# LPC1768_0.net
KiCad netlist of a schematic drawn in Altium Designer
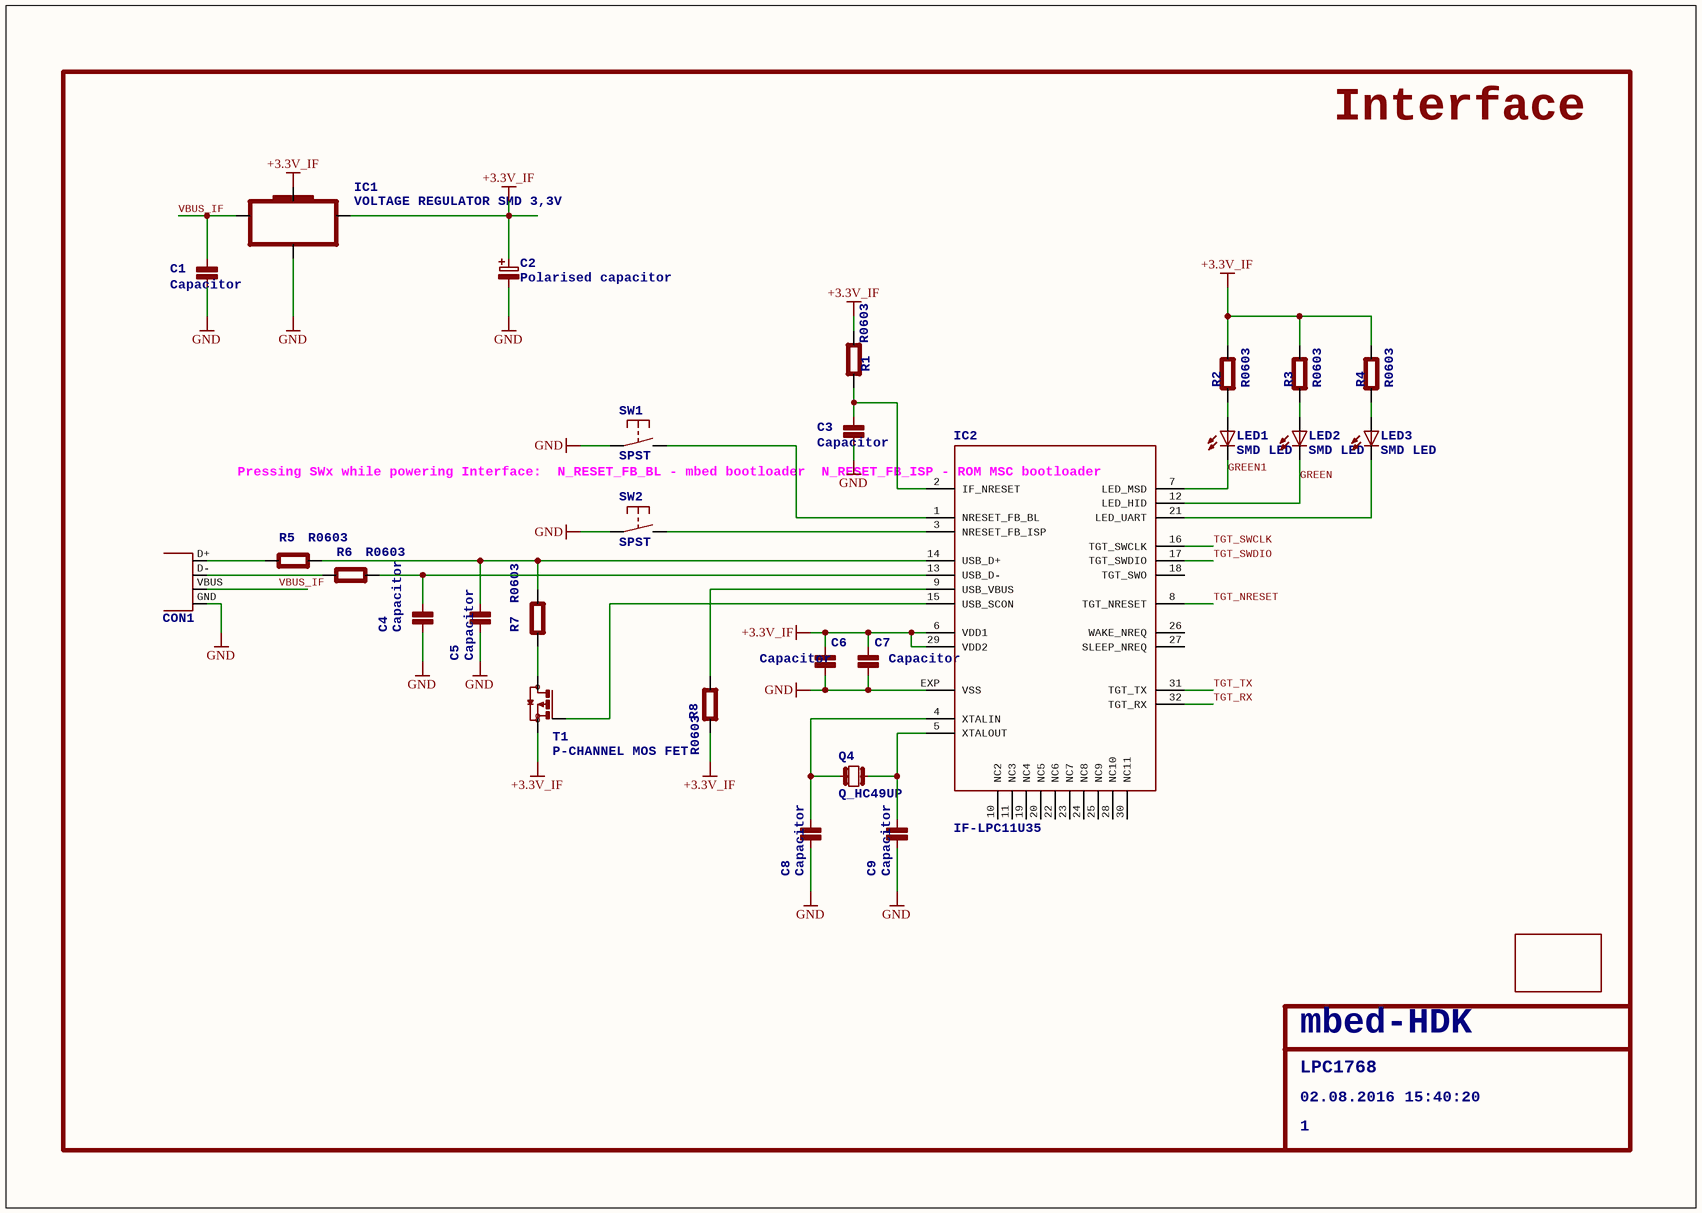
[diagram p0: LPC1768_0.SchDoc]

(export (version "E")
  (design (tool "Eeschema 10.0.6"))
  (components
    (comp (ref "C1") (value "Capacitor") (footprint "0603") (libsource (lib "mbed-HDK") (part "C0603")))
    (comp (ref "C2")
      (value "Polarised capacitor")
      (footprint "CASE-B")
      (libsource (lib "mbed-HDK") (part "C-POLB"))
    )
    (comp (ref "C3") (value "Capacitor") (footprint "0603") (libsource (lib "mbed-HDK") (part "C0603")))
    (comp (ref "C4") (value "Capacitor") (footprint "0603") (libsource (lib "") (part "C0603_1")))
    (comp (ref "C5") (value "Capacitor") (footprint "0603") (libsource (lib "") (part "C0603_1")))
    (comp (ref "C6") (value "Capacitor") (footprint "0603") (libsource (lib "mbed-HDK") (part "C0603")))
    (comp (ref "C7") (value "Capacitor") (footprint "0603") (libsource (lib "mbed-HDK") (part "C0603")))
    (comp (ref "C8") (value "Capacitor") (footprint "0603") (libsource (lib "") (part "C0603_1")))
    (comp (ref "C9") (value "Capacitor") (footprint "0603") (libsource (lib "") (part "C0603_1")))
    (comp (ref "CON1")
      (value "USB Connectors")
      (footprint "USB-MB-S")
      (libsource (lib "mbed-HDK") (part "USB-MB-S"))
    )
    (comp (ref "IC1")
      (value "VOLTAGE REGULATOR SMD 3,3V")
      (footprint "SOT223")
      (libsource (lib "mbed-HDK") (part "LD1117S33"))
    )
    (comp (ref "IC2")
      (value "IF-LPC11U35")
      (footprint "HVQFN33")
      (libsource (lib "mbed-HDK") (part "IF-LPC11U35"))
    )
    (comp (ref "LED1")
      (value "SMD LED")
      (footprint "CHIPLED_0603")
      (libsource (lib "mbed-HDK") (part "LED0603"))
    )
    (comp (ref "LED2")
      (value "SMD LED")
      (footprint "CHIPLED_0603")
      (libsource (lib "mbed-HDK") (part "LED0603"))
    )
    (comp (ref "LED3")
      (value "SMD LED")
      (footprint "CHIPLED_0603")
      (libsource (lib "mbed-HDK") (part "LED0603"))
    )
    (comp (ref "Q4") (value "Q_HC49UP") (footprint "HC49UP") (libsource (lib "mbed-HDK") (part "Q_HC49UP")))
    (comp (ref "R1") (value "R0603") (footprint "0603") (libsource (lib "mbed-HDK") (part "R0603")))
    (comp (ref "R2") (value "R0603") (footprint "0603") (libsource (lib "mbed-HDK") (part "R0603")))
    (comp (ref "R3") (value "R0603") (footprint "0603") (libsource (lib "mbed-HDK") (part "R0603")))
    (comp (ref "R4") (value "R0603") (footprint "0603") (libsource (lib "mbed-HDK") (part "R0603")))
    (comp (ref "R5") (value "R0603") (footprint "0603") (libsource (lib "mbed-HDK") (part "R0603")))
    (comp (ref "R6") (value "R0603") (footprint "0603") (libsource (lib "mbed-HDK") (part "R0603")))
    (comp (ref "R7") (value "R0603") (footprint "0603") (libsource (lib "mbed-HDK") (part "R0603")))
    (comp (ref "R8") (value "R0603") (footprint "0603") (libsource (lib "mbed-HDK") (part "R0603")))
    (comp (ref "SS1")
      (value "MBED-ENABLED-LOGOMEDIUM")
      (footprint "MBED-ENABLED-LOGO-500X500-MIL")
      (libsource (lib "mbed-HDK") (part "MBED-ENABLED-LOGOMEDIUM"))
    )
    (comp (ref "SW1") (value "SPST") (footprint "DTSM-32S-B") (libsource (lib "mbed-HDK") (part "SPST")))
    (comp (ref "SW2") (value "SPST") (footprint "DTSM-32S-B") (libsource (lib "mbed-HDK") (part "SPST")))
    (comp (ref "T1")
      (value "P-CHANNEL MOS FET")
      (footprint "SOT23")
      (libsource (lib "mbed-HDK") (part "BSS84"))
    )
  )
  (nets
    (net (code "1") (name "+3.3V_IF") (class "Default")
      (node (ref "C2") (pin "1") (pinfunction "1_1") (pintype "passive"))
      (node (ref "C6") (pin "1") (pinfunction "P$1_1") (pintype "passive"))
      (node (ref "C7") (pin "1") (pinfunction "P$1_1") (pintype "passive"))
      (node (ref "IC1") (pin "2") (pinfunction "OUT_2") (pintype "passive"))
      (node (ref "IC1") (pin "4") (pinfunction "K_4") (pintype "passive"))
      (node (ref "IC2") (pin "29") (pinfunction "VDD2_29") (pintype "passive"))
      (node (ref "IC2") (pin "6") (pinfunction "VDD1_6") (pintype "passive"))
      (node (ref "R1") (pin "2") (pinfunction "P$2_2") (pintype "passive"))
      (node (ref "R2") (pin "1") (pinfunction "P$1_1") (pintype "passive"))
      (node (ref "R3") (pin "1") (pinfunction "P$1_1") (pintype "passive"))
      (node (ref "R4") (pin "1") (pinfunction "P$1_1") (pintype "passive"))
      (node (ref "R8") (pin "2") (pinfunction "P$2_2") (pintype "passive"))
      (node (ref "T1") (pin "2") (pinfunction "S_2") (pintype "passive"))
    )
    (net (code "2") (name "/GREEN") (class "Default")
      (node (ref "IC2") (pin "12") (pinfunction "LED_HID_12") (pintype "passive"))
      (node (ref "LED2") (pin "C") (pinfunction "C_C") (pintype "passive"))
    )
    (net (code "3") (name "/GREEN1") (class "Default")
      (node (ref "IC2") (pin "7") (pinfunction "LED_MSD_7") (pintype "passive"))
      (node (ref "LED1") (pin "C") (pinfunction "C_C") (pintype "passive"))
    )
    (net (code "4") (name "/TGT_NRESET") (class "Default")
      (node (ref "IC2") (pin "8") (pinfunction "TGT_NRESET_8") (pintype "passive"))
    )
    (net (code "5") (name "/TGT_RX") (class "Default")
      (node (ref "IC2") (pin "32") (pinfunction "TGT_RX_32") (pintype "passive"))
    )
    (net (code "6") (name "/TGT_SWCLK") (class "Default")
      (node (ref "IC2") (pin "16") (pinfunction "TGT_SWCLK_16") (pintype "passive"))
    )
    (net (code "7") (name "/TGT_SWDIO") (class "Default")
      (node (ref "IC2") (pin "17") (pinfunction "TGT_SWDIO_17") (pintype "passive"))
    )
    (net (code "8") (name "/TGT_TX") (class "Default")
      (node (ref "IC2") (pin "31") (pinfunction "TGT_TX_31") (pintype "passive"))
    )
    (net (code "9") (name "/VBUS_IF") (class "Default")
      (node (ref "C1") (pin "1") (pinfunction "P$1_1") (pintype "passive"))
      (node (ref "CON1") (pin "VBUS") (pinfunction "VBUS_VBUS") (pintype "passive"))
      (node (ref "IC1") (pin "3") (pinfunction "IN_3") (pintype "passive"))
    )
    (net (code "10") (name "GND") (class "Default")
      (node (ref "C1") (pin "2") (pinfunction "P$2_2") (pintype "passive"))
      (node (ref "C2") (pin "2") (pinfunction "2_2") (pintype "passive"))
      (node (ref "C3") (pin "2") (pinfunction "P$2_2") (pintype "passive"))
      (node (ref "C4") (pin "2") (pinfunction "P$2_2") (pintype "passive"))
      (node (ref "C5") (pin "2") (pinfunction "P$2_2") (pintype "passive"))
      (node (ref "C6") (pin "2") (pinfunction "P$2_2") (pintype "passive"))
      (node (ref "C7") (pin "2") (pinfunction "P$2_2") (pintype "passive"))
      (node (ref "C8") (pin "2") (pinfunction "P$2_2") (pintype "passive"))
      (node (ref "C9") (pin "2") (pinfunction "P$2_2") (pintype "passive"))
      (node (ref "CON1") (pin "GND") (pinfunction "GND_GND") (pintype "passive"))
      (node (ref "IC1") (pin "1") (pinfunction "GND_1") (pintype "passive"))
      (node (ref "IC2") (pin "EXP") (pinfunction "VSS_EXP") (pintype "passive"))
      (node (ref "SW1") (pin "P$1") (pinfunction "P_P$1") (pintype "passive"))
      (node (ref "SW2") (pin "P$1") (pinfunction "P_P$1") (pintype "passive"))
    )
    (net (code "11") (name "Net-(C3-P$1)") (class "Default")
      (node (ref "C3") (pin "1") (pinfunction "P$1_1") (pintype "passive"))
      (node (ref "IC2") (pin "2") (pinfunction "IF_NRESET_2") (pintype "passive"))
      (node (ref "R1") (pin "1") (pinfunction "P$1_1") (pintype "passive"))
    )
    (net (code "12") (name "Net-(C4-P$1)") (class "Default")
      (node (ref "C4") (pin "1") (pinfunction "P$1_1") (pintype "passive"))
      (node (ref "IC2") (pin "13") (pinfunction "USB_D-_13") (pintype "passive"))
      (node (ref "R6") (pin "2") (pinfunction "P$2_2") (pintype "passive"))
    )
    (net (code "13") (name "Net-(C5-P$1)") (class "Default")
      (node (ref "C5") (pin "1") (pinfunction "P$1_1") (pintype "passive"))
      (node (ref "IC2") (pin "14") (pinfunction "USB_D+_14") (pintype "passive"))
      (node (ref "R5") (pin "2") (pinfunction "P$2_2") (pintype "passive"))
      (node (ref "R7") (pin "2") (pinfunction "P$2_2") (pintype "passive"))
    )
    (net (code "14") (name "Net-(C8-P$1)") (class "Default")
      (node (ref "C8") (pin "1") (pinfunction "P$1_1") (pintype "passive"))
      (node (ref "IC2") (pin "4") (pinfunction "XTALIN_4") (pintype "passive"))
      (node (ref "Q4") (pin "1") (pinfunction "1_1") (pintype "passive"))
    )
    (net (code "15") (name "Net-(C9-P$1)") (class "Default")
      (node (ref "C9") (pin "1") (pinfunction "P$1_1") (pintype "passive"))
      (node (ref "IC2") (pin "5") (pinfunction "XTALOUT_5") (pintype "passive"))
      (node (ref "Q4") (pin "2") (pinfunction "2_2") (pintype "passive"))
    )
    (net (code "16") (name "Net-(IC2-LED_UART)") (class "Default")
      (node (ref "IC2") (pin "21") (pinfunction "LED_UART_21") (pintype "passive"))
      (node (ref "LED3") (pin "C") (pinfunction "C_C") (pintype "passive"))
    )
    (net (code "17") (name "Net-(IC2-NRESET_FB_BL)") (class "Default")
      (node (ref "IC2") (pin "1") (pinfunction "NRESET_FB_BL_1") (pintype "passive"))
      (node (ref "SW1") (pin "P$2") (pinfunction "S_P$2") (pintype "passive"))
    )
    (net (code "18") (name "Net-(IC2-NRESET_FB_ISP)") (class "Default")
      (node (ref "IC2") (pin "3") (pinfunction "NRESET_FB_ISP_3") (pintype "passive"))
      (node (ref "SW2") (pin "P$2") (pinfunction "S_P$2") (pintype "passive"))
    )
    (net (code "19") (name "Net-(IC2-USB_SCON)") (class "Default")
      (node (ref "IC2") (pin "15") (pinfunction "USB_SCON_15") (pintype "passive"))
      (node (ref "T1") (pin "1") (pinfunction "G_1") (pintype "passive"))
    )
    (net (code "20") (name "Net-(IC2-USB_VBUS)") (class "Default")
      (node (ref "IC2") (pin "9") (pinfunction "USB_VBUS_9") (pintype "passive"))
      (node (ref "R8") (pin "1") (pinfunction "P$1_1") (pintype "passive"))
    )
    (net (code "21") (name "Net-(R2-P$2)") (class "Default")
      (node (ref "LED1") (pin "A") (pinfunction "A_A") (pintype "passive"))
      (node (ref "R2") (pin "2") (pinfunction "P$2_2") (pintype "passive"))
    )
    (net (code "22") (name "Net-(R3-P$2)") (class "Default")
      (node (ref "LED2") (pin "A") (pinfunction "A_A") (pintype "passive"))
      (node (ref "R3") (pin "2") (pinfunction "P$2_2") (pintype "passive"))
    )
    (net (code "23") (name "Net-(R4-P$2)") (class "Default")
      (node (ref "LED3") (pin "A") (pinfunction "A_A") (pintype "passive"))
      (node (ref "R4") (pin "2") (pinfunction "P$2_2") (pintype "passive"))
    )
    (net (code "24") (name "Net-(R5-P$1)") (class "Default")
      (node (ref "CON1") (pin "D+") (pinfunction "D+_D+") (pintype "passive"))
      (node (ref "R5") (pin "1") (pinfunction "P$1_1") (pintype "passive"))
    )
    (net (code "25") (name "Net-(R6-P$1)") (class "Default")
      (node (ref "CON1") (pin "D-") (pinfunction "D-_D-") (pintype "passive"))
      (node (ref "R6") (pin "1") (pinfunction "P$1_1") (pintype "passive"))
    )
    (net (code "26") (name "Net-(R7-P$1)") (class "Default")
      (node (ref "R7") (pin "1") (pinfunction "P$1_1") (pintype "passive"))
      (node (ref "T1") (pin "3") (pinfunction "D_3") (pintype "passive"))
    )
    (net (code "27") (name "unconnected-(IC2-NC2-Pad10)") (class "Default")
      (node (ref "IC2") (pin "10") (pinfunction "NC2_10") (pintype "passive"))
    )
    (net (code "28") (name "unconnected-(IC2-NC3-Pad11)") (class "Default")
      (node (ref "IC2") (pin "11") (pinfunction "NC3_11") (pintype "passive"))
    )
    (net (code "29") (name "unconnected-(IC2-NC4-Pad19)") (class "Default")
      (node (ref "IC2") (pin "19") (pinfunction "NC4_19") (pintype "passive"))
    )
    (net (code "30") (name "unconnected-(IC2-NC5-Pad20)") (class "Default")
      (node (ref "IC2") (pin "20") (pinfunction "NC5_20") (pintype "passive"))
    )
    (net (code "31") (name "unconnected-(IC2-NC6-Pad22)") (class "Default")
      (node (ref "IC2") (pin "22") (pinfunction "NC6_22") (pintype "passive"))
    )
    (net (code "32") (name "unconnected-(IC2-NC7-Pad23)") (class "Default")
      (node (ref "IC2") (pin "23") (pinfunction "NC7_23") (pintype "passive"))
    )
    (net (code "33") (name "unconnected-(IC2-NC8-Pad24)") (class "Default")
      (node (ref "IC2") (pin "24") (pinfunction "NC8_24") (pintype "passive"))
    )
    (net (code "34") (name "unconnected-(IC2-NC9-Pad25)") (class "Default")
      (node (ref "IC2") (pin "25") (pinfunction "NC9_25") (pintype "passive"))
    )
    (net (code "35") (name "unconnected-(IC2-NC10-Pad28)") (class "Default")
      (node (ref "IC2") (pin "28") (pinfunction "NC10_28") (pintype "passive"))
    )
    (net (code "36") (name "unconnected-(IC2-NC11-Pad30)") (class "Default")
      (node (ref "IC2") (pin "30") (pinfunction "NC11_30") (pintype "passive"))
    )
    (net (code "37") (name "unconnected-(IC2-SLEEP_NREQ-Pad27)") (class "Default")
      (node (ref "IC2") (pin "27") (pinfunction "SLEEP_NREQ_27") (pintype "passive"))
    )
    (net (code "38") (name "unconnected-(IC2-TGT_SWO-Pad18)") (class "Default")
      (node (ref "IC2") (pin "18") (pinfunction "TGT_SWO_18") (pintype "passive"))
    )
    (net (code "39") (name "unconnected-(IC2-WAKE_NREQ-Pad26)") (class "Default")
      (node (ref "IC2") (pin "26") (pinfunction "WAKE_NREQ_26") (pintype "passive"))
    )
  )
)
